# Iridium_9603_Lite_USB.net
KiCad netlist of a schematic drawn in EAGLE
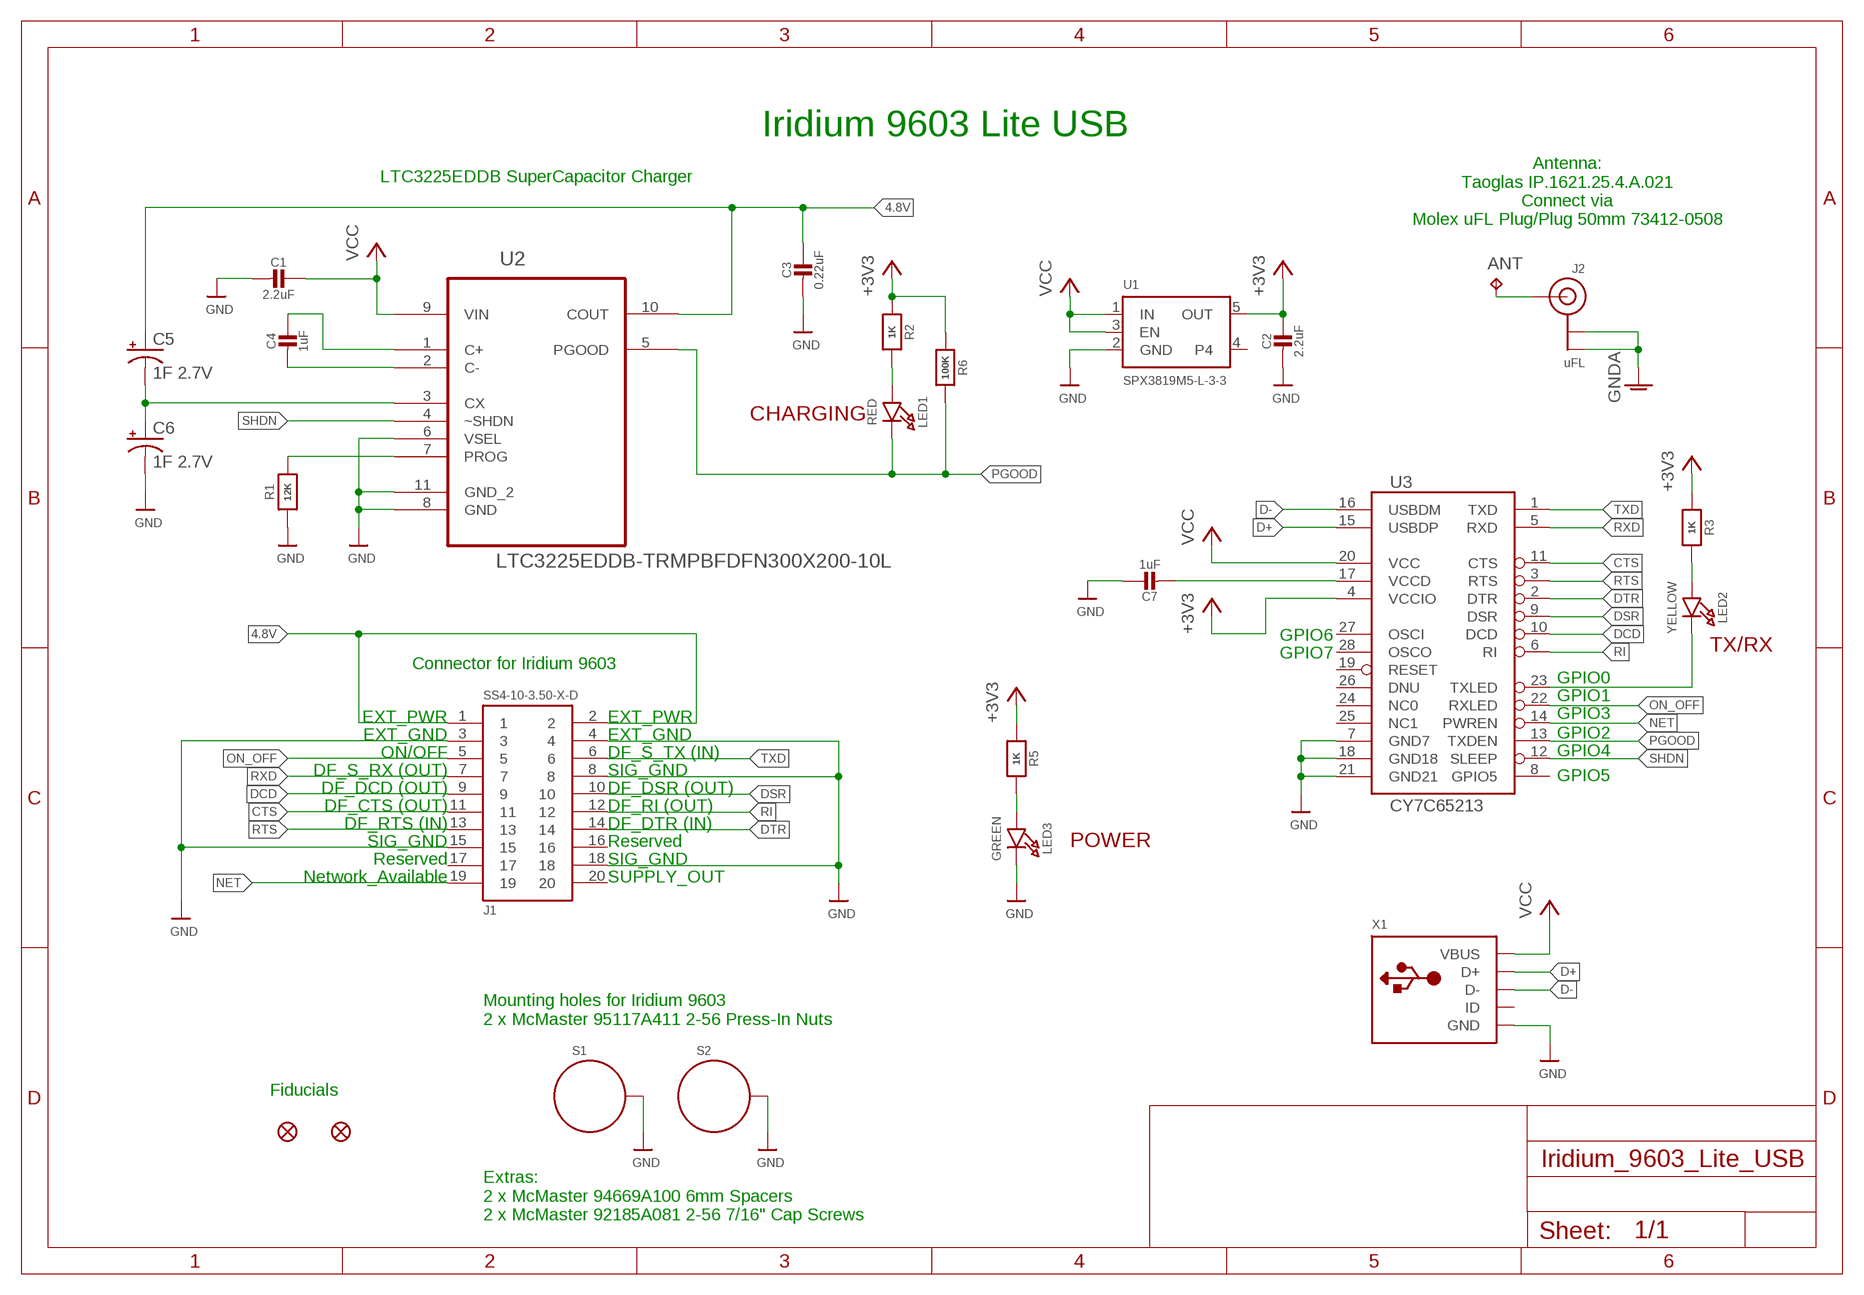
[diagram p0: schematic, sheet 1]

(export (version "E")
  (design (tool "Eeschema 10.0.6"))
  (components
    (comp (ref "ANT")
      (value "TPB2,54")
      (footprint "eagle-import:B2,54")
      (libsource (lib "eagle-import") (part "TPB2,54"))
    )
    (comp (ref "C1")
      (value "2.2uF")
      (footprint "eagle-import:0805-NO")
      (libsource (lib "eagle-import") (part "CAP_CERAMIC0805-NOOUTLINE"))
    )
    (comp (ref "C2")
      (value "2.2uF")
      (footprint "eagle-import:0805-NO")
      (libsource (lib "eagle-import") (part "CAP_CERAMIC0805-NOOUTLINE"))
    )
    (comp (ref "C3")
      (value "0.22uF")
      (footprint "eagle-import:0603-NO")
      (libsource (lib "eagle-import") (part "CAP_CERAMIC0603_NO"))
    )
    (comp (ref "C4")
      (value "1uF")
      (footprint "eagle-import:0603-NO")
      (libsource (lib "eagle-import") (part "CAP_CERAMIC0603_NO"))
    )
    (comp (ref "C5")
      (value "1F 2.7V")
      (footprint "eagle-import:CPOL-RADIAL-1F-2.7V")
      (libsource (lib "eagle-import") (part "1F-2.7V(PTH)CPOL-RADIAL-1H-2.7V"))
    )
    (comp (ref "C6")
      (value "1F 2.7V")
      (footprint "eagle-import:CPOL-RADIAL-1F-2.7V")
      (libsource (lib "eagle-import") (part "1F-2.7V(PTH)CPOL-RADIAL-1H-2.7V"))
    )
    (comp (ref "C7")
      (value "1uF")
      (footprint "eagle-import:0603-NO")
      (libsource (lib "eagle-import") (part "CAP_CERAMIC0603_NO"))
    )
    (comp (ref "FD1")
      (value "FIDUCIAL1X2")
      (footprint "eagle-import:FIDUCIAL-1X2")
      (libsource (lib "eagle-import") (part "FIDUCIAL1X2"))
    )
    (comp (ref "FD2")
      (value "FIDUCIAL1X2")
      (footprint "eagle-import:FIDUCIAL-1X2")
      (libsource (lib "eagle-import") (part "FIDUCIAL1X2"))
    )
    (comp (ref "J1")
      (value "SS4-10-3.50-X-D")
      (footprint "eagle-import:SS4-10-3.50-X-D")
      (libsource (lib "eagle-import") (part "SS4-10-3.50-X-D"))
    )
    (comp (ref "J2")
      (value "uFL")
      (footprint "eagle-import:U.FL")
      (libsource (lib "eagle-import") (part "ANTENNA_U.FL"))
    )
    (comp (ref "LED1")
      (value "RED")
      (footprint "eagle-import:CHIPLED_0805_NOOUTLINE")
      (libsource (lib "eagle-import") (part "LED0805_NOOUTLINE"))
    )
    (comp (ref "LED2")
      (value "YELLOW")
      (footprint "eagle-import:CHIPLED_0805_NOOUTLINE")
      (libsource (lib "eagle-import") (part "LED0805_NOOUTLINE"))
    )
    (comp (ref "LED3")
      (value "GREEN")
      (footprint "eagle-import:CHIPLED_0805_NOOUTLINE")
      (libsource (lib "eagle-import") (part "LED0805_NOOUTLINE"))
    )
    (comp (ref "R1")
      (value "12K")
      (footprint "eagle-import:0805-NO")
      (libsource (lib "eagle-import") (part "RESISTOR0805_NOOUTLINE"))
    )
    (comp (ref "R2")
      (value "1K")
      (footprint "eagle-import:0603-NO")
      (libsource (lib "eagle-import") (part "RESISTOR_0603_NOOUT"))
    )
    (comp (ref "R3")
      (value "1K")
      (footprint "eagle-import:0603-NO")
      (libsource (lib "eagle-import") (part "RESISTOR_0603_NOOUT"))
    )
    (comp (ref "R5")
      (value "1K")
      (footprint "eagle-import:0603-NO")
      (libsource (lib "eagle-import") (part "RESISTOR_0603_NOOUT"))
    )
    (comp (ref "R6")
      (value "100K")
      (footprint "eagle-import:0603-NO")
      (libsource (lib "eagle-import") (part "RESISTOR_0603_NOOUT"))
    )
    (comp (ref "S1")
      (value "STANDOFF_ELECTRICALMCMASTER-95117A411")
      (footprint "eagle-import:STANDOFF-ELECTRICAL-MCMASTER-95117A411")
      (libsource (lib "eagle-import") (part "STANDOFF_ELECTRICALMCMASTER-95117A411"))
    )
    (comp (ref "S2")
      (value "STANDOFF_ELECTRICALMCMASTER-95117A411")
      (footprint "eagle-import:STANDOFF-ELECTRICAL-MCMASTER-95117A411")
      (libsource (lib "eagle-import") (part "STANDOFF_ELECTRICALMCMASTER-95117A411"))
    )
    (comp (ref "U1")
      (value "SPX3819M5-L-3-3")
      (footprint "eagle-import:SOT23-5")
      (libsource (lib "eagle-import") (part "VREG_SOT23-5"))
    )
    (comp (ref "U2")
      (value "LTC3225EDDB-TRMPBFDFN300X200-10L")
      (footprint "eagle-import:DFN300X200-10L")
      (libsource (lib "eagle-import") (part "LTC3225EDDB-TRMPBFDFN300X200-10L"))
    )
    (comp (ref "U3")
      (value "CY7C65213")
      (footprint "eagle-import:SSOP28DB")
      (libsource (lib "eagle-import") (part "CY7C65213"))
    )
    (comp (ref "X1")
      (value "USBFCI_10103594_MILL")
      (footprint "eagle-import:FCI_10103594_MILL")
      (libsource (lib "eagle-import") (part "USBFCI_10103594_MILL"))
    )
  )
  (nets
    (net (code "1") (name "+3V3") (class "Default")
      (node (ref "C2") (pin "1") (pinfunction "1_1") (pintype "passive"))
      (node (ref "R2") (pin "1") (pinfunction "1_1") (pintype "passive"))
      (node (ref "R3") (pin "1") (pinfunction "1_1") (pintype "passive"))
      (node (ref "R5") (pin "1") (pinfunction "1_1") (pintype "passive"))
      (node (ref "R6") (pin "1") (pinfunction "1_1") (pintype "passive"))
      (node (ref "U1") (pin "5") (pinfunction "OUT_5") (pintype "power_in"))
      (node (ref "U3") (pin "4") (pinfunction "VCCIO_4") (pintype "power_in"))
    )
    (net (code "2") (name "/NC1") (class "Default")
      (node (ref "U3") (pin "25") (pinfunction "NC1_25") (pintype "power_in"))
    )
    (net (code "3") (name "4.8V") (class "Default")
      (node (ref "C3") (pin "1") (pinfunction "1_1") (pintype "passive"))
      (node (ref "C5") (pin "+") (pinfunction "+_+") (pintype "passive"))
      (node (ref "J1") (pin "1") (pinfunction "1_1") (pintype "bidirectional"))
      (node (ref "J1") (pin "2") (pinfunction "2_2") (pintype "bidirectional"))
      (node (ref "U2") (pin "10") (pinfunction "COUT_10") (pintype "output"))
    )
    (net (code "4") (name "CTS") (class "Default")
      (node (ref "J1") (pin "11") (pinfunction "11_11") (pintype "bidirectional"))
      (node (ref "U3") (pin "11") (pinfunction "CTS_11") (pintype "input"))
    )
    (net (code "5") (name "D+") (class "Default")
      (node (ref "U3") (pin "15") (pinfunction "USBDP_15") (pintype "bidirectional"))
      (node (ref "X1") (pin "D+") (pinfunction "D+_D+") (pintype "bidirectional"))
    )
    (net (code "6") (name "D-") (class "Default")
      (node (ref "U3") (pin "16") (pinfunction "USBDM_16") (pintype "bidirectional"))
      (node (ref "X1") (pin "D-") (pinfunction "D-_D-") (pintype "bidirectional"))
    )
    (net (code "7") (name "DCD") (class "Default")
      (node (ref "J1") (pin "9") (pinfunction "9_9") (pintype "bidirectional"))
      (node (ref "U3") (pin "10") (pinfunction "DCD_10") (pintype "input"))
    )
    (net (code "8") (name "DSR") (class "Default")
      (node (ref "J1") (pin "10") (pinfunction "10_10") (pintype "bidirectional"))
      (node (ref "U3") (pin "9") (pinfunction "DSR_9") (pintype "input"))
    )
    (net (code "9") (name "DTR") (class "Default")
      (node (ref "J1") (pin "14") (pinfunction "14_14") (pintype "bidirectional"))
      (node (ref "U3") (pin "2") (pinfunction "DTR_2") (pintype "output"))
    )
    (net (code "10") (name "GND") (class "Default")
      (node (ref "C1") (pin "2") (pinfunction "2_2") (pintype "passive"))
      (node (ref "C2") (pin "2") (pinfunction "2_2") (pintype "passive"))
      (node (ref "C3") (pin "2") (pinfunction "2_2") (pintype "passive"))
      (node (ref "C6") (pin "-") (pinfunction "-_-") (pintype "passive"))
      (node (ref "C7") (pin "1") (pinfunction "1_1") (pintype "passive"))
      (node (ref "J1") (pin "15") (pinfunction "15_15") (pintype "bidirectional"))
      (node (ref "J1") (pin "18") (pinfunction "18_18") (pintype "bidirectional"))
      (node (ref "J1") (pin "3") (pinfunction "3_3") (pintype "bidirectional"))
      (node (ref "J1") (pin "4") (pinfunction "4_4") (pintype "bidirectional"))
      (node (ref "J1") (pin "8") (pinfunction "8_8") (pintype "bidirectional"))
      (node (ref "LED3") (pin "C") (pinfunction "C_C") (pintype "passive"))
      (node (ref "R1") (pin "1") (pinfunction "1_1") (pintype "passive"))
      (node (ref "S1") (pin "P1") (pinfunction "P$1_P1") (pintype "bidirectional"))
      (node (ref "S2") (pin "P1") (pinfunction "P$1_P1") (pintype "bidirectional"))
      (node (ref "U1") (pin "2") (pinfunction "GND_2") (pintype "power_in"))
      (node (ref "U2") (pin "11") (pinfunction "GND_2_11") (pintype "passive"))
      (node (ref "U2") (pin "6") (pinfunction "VSEL_6") (pintype "input"))
      (node (ref "U2") (pin "8") (pinfunction "GND_8") (pintype "passive"))
      (node (ref "U3") (pin "18") (pinfunction "GND18_18") (pintype "power_in"))
      (node (ref "U3") (pin "21") (pinfunction "GND21_21") (pintype "power_in"))
      (node (ref "U3") (pin "7") (pinfunction "GND7_7") (pintype "power_in"))
      (node (ref "X1") (pin "BASE@1") (pinfunction "GND_BASE@1") (pintype "power_in"))
      (node (ref "X1") (pin "BASE@2") (pinfunction "GND_BASE@2") (pintype "power_in"))
      (node (ref "X1") (pin "GND") (pinfunction "GND_GND") (pintype "power_in"))
      (node (ref "X1") (pin "SPRT@1") (pinfunction "GND_SPRT@1") (pintype "power_in"))
      (node (ref "X1") (pin "SPRT@2") (pinfunction "GND_SPRT@2") (pintype "power_in"))
      (node (ref "X1") (pin "SPRT@3") (pinfunction "GND_SPRT@3") (pintype "power_in"))
      (node (ref "X1") (pin "SPRT@4") (pinfunction "GND_SPRT@4") (pintype "power_in"))
    )
    (net (code "11") (name "GNDA") (class "Default")
      (node (ref "J2") (pin "1") (pinfunction "GND_1") (pintype "passive"))
      (node (ref "J2") (pin "2") (pinfunction "GND_2") (pintype "passive"))
    )
    (net (code "12") (name "NET") (class "Default")
      (node (ref "J1") (pin "19") (pinfunction "19_19") (pintype "bidirectional"))
      (node (ref "U3") (pin "14") (pinfunction "PWREN_14") (pintype "input"))
    )
    (net (code "13") (name "Net-(J2-SIGNAL)") (class "Default")
      (node (ref "ANT") (pin "TP") (pinfunction "TP_TP") (pintype "input"))
      (node (ref "J2") (pin "3") (pinfunction "SIGNAL_3") (pintype "passive"))
    )
    (net (code "14") (name "Net-(LED1-PadA)") (class "Default")
      (node (ref "LED1") (pin "A") (pinfunction "A_A") (pintype "passive"))
      (node (ref "R2") (pin "2") (pinfunction "2_2") (pintype "passive"))
    )
    (net (code "15") (name "Net-(LED2-PadA)") (class "Default")
      (node (ref "LED2") (pin "A") (pinfunction "A_A") (pintype "passive"))
      (node (ref "R3") (pin "2") (pinfunction "2_2") (pintype "passive"))
    )
    (net (code "16") (name "Net-(LED3-PadA)") (class "Default")
      (node (ref "LED3") (pin "A") (pinfunction "A_A") (pintype "passive"))
      (node (ref "R5") (pin "2") (pinfunction "2_2") (pintype "passive"))
    )
    (net (code "17") (name "Net-(U2-C+)") (class "Default")
      (node (ref "C4") (pin "1") (pinfunction "1_1") (pintype "passive"))
      (node (ref "U2") (pin "1") (pinfunction "C+_1") (pintype "passive"))
    )
    (net (code "18") (name "Net-(U2-C-)") (class "Default")
      (node (ref "C4") (pin "2") (pinfunction "2_2") (pintype "passive"))
      (node (ref "U2") (pin "2") (pinfunction "C-_2") (pintype "passive"))
    )
    (net (code "19") (name "Net-(U2-CX)") (class "Default")
      (node (ref "C5") (pin "-") (pinfunction "-_-") (pintype "passive"))
      (node (ref "C6") (pin "+") (pinfunction "+_+") (pintype "passive"))
      (node (ref "U2") (pin "3") (pinfunction "CX_3") (pintype "passive"))
    )
    (net (code "20") (name "Net-(U2-PROG)") (class "Default")
      (node (ref "R1") (pin "2") (pinfunction "2_2") (pintype "passive"))
      (node (ref "U2") (pin "7") (pinfunction "PROG_7") (pintype "input"))
    )
    (net (code "21") (name "Net-(U3-TXLED)") (class "Default")
      (node (ref "LED2") (pin "C") (pinfunction "C_C") (pintype "passive"))
      (node (ref "U3") (pin "23") (pinfunction "TXLED_23") (pintype "input"))
    )
    (net (code "22") (name "Net-(U3-VCCD)") (class "Default")
      (node (ref "C7") (pin "2") (pinfunction "2_2") (pintype "passive"))
      (node (ref "U3") (pin "17") (pinfunction "VCCD_17") (pintype "output"))
    )
    (net (code "23") (name "ON_OFF") (class "Default")
      (node (ref "J1") (pin "5") (pinfunction "5_5") (pintype "bidirectional"))
      (node (ref "U3") (pin "22") (pinfunction "RXLED_22") (pintype "input"))
    )
    (net (code "24") (name "PGOOD") (class "Default")
      (node (ref "LED1") (pin "C") (pinfunction "C_C") (pintype "passive"))
      (node (ref "R6") (pin "2") (pinfunction "2_2") (pintype "passive"))
      (node (ref "U2") (pin "5") (pinfunction "PGOOD_5") (pintype "output"))
      (node (ref "U3") (pin "13") (pinfunction "TXDEN_13") (pintype "input"))
    )
    (net (code "25") (name "RI") (class "Default")
      (node (ref "J1") (pin "12") (pinfunction "12_12") (pintype "bidirectional"))
      (node (ref "U3") (pin "6") (pinfunction "RI_6") (pintype "input"))
    )
    (net (code "26") (name "RTS") (class "Default")
      (node (ref "J1") (pin "13") (pinfunction "13_13") (pintype "bidirectional"))
      (node (ref "U3") (pin "3") (pinfunction "RTS_3") (pintype "output"))
    )
    (net (code "27") (name "RXD") (class "Default")
      (node (ref "J1") (pin "7") (pinfunction "7_7") (pintype "bidirectional"))
      (node (ref "U3") (pin "5") (pinfunction "RXD_5") (pintype "input"))
    )
    (net (code "28") (name "SHDN") (class "Default")
      (node (ref "U2") (pin "4") (pinfunction "~{SHDN}_4") (pintype "input"))
      (node (ref "U3") (pin "12") (pinfunction "SLEEP_12") (pintype "input"))
    )
    (net (code "29") (name "TXD") (class "Default")
      (node (ref "J1") (pin "6") (pinfunction "6_6") (pintype "bidirectional"))
      (node (ref "U3") (pin "1") (pinfunction "TXD_1") (pintype "output"))
    )
    (net (code "30") (name "VCC") (class "Default")
      (node (ref "C1") (pin "1") (pinfunction "1_1") (pintype "passive"))
      (node (ref "U1") (pin "1") (pinfunction "IN_1") (pintype "power_in"))
      (node (ref "U1") (pin "3") (pinfunction "EN_3") (pintype "input"))
      (node (ref "U2") (pin "9") (pinfunction "VIN_9") (pintype "power_in"))
      (node (ref "U3") (pin "20") (pinfunction "VCC_20") (pintype "power_in"))
      (node (ref "X1") (pin "VBUS") (pinfunction "VBUS_VBUS") (pintype "power_in"))
    )
    (net (code "31") (name "unconnected-(J1-Pad16)") (class "Default")
      (node (ref "J1") (pin "16") (pinfunction "16_16") (pintype "bidirectional"))
    )
    (net (code "32") (name "unconnected-(J1-Pad17)") (class "Default")
      (node (ref "J1") (pin "17") (pinfunction "17_17") (pintype "bidirectional"))
    )
    (net (code "33") (name "unconnected-(J1-Pad20)") (class "Default")
      (node (ref "J1") (pin "20") (pinfunction "20_20") (pintype "bidirectional"))
    )
    (net (code "34") (name "unconnected-(U1-P4-Pad4)") (class "Default")
      (node (ref "U1") (pin "4") (pinfunction "P4_4") (pintype "bidirectional"))
    )
    (net (code "35") (name "unconnected-(U3-DNU-Pad26)") (class "Default")
      (node (ref "U3") (pin "26") (pinfunction "DNU_26") (pintype "input"))
    )
    (net (code "36") (name "unconnected-(U3-GPIO5-Pad8)") (class "Default")
      (node (ref "U3") (pin "8") (pinfunction "GPIO5_8") (pintype "input"))
    )
    (net (code "37") (name "unconnected-(U3-NC0-Pad24)") (class "Default")
      (node (ref "U3") (pin "24") (pinfunction "NC0_24") (pintype "input"))
    )
    (net (code "38") (name "unconnected-(U3-OSCI-Pad27)") (class "Default")
      (node (ref "U3") (pin "27") (pinfunction "OSCI_27") (pintype "input"))
    )
    (net (code "39") (name "unconnected-(U3-OSCO-Pad28)") (class "Default")
      (node (ref "U3") (pin "28") (pinfunction "OSCO_28") (pintype "output"))
    )
    (net (code "40") (name "unconnected-(U3-RESET-Pad19)") (class "Default")
      (node (ref "U3") (pin "19") (pinfunction "RESET_19") (pintype "input"))
    )
    (net (code "41") (name "unconnected-(X1-PadID)") (class "Default")
      (node (ref "X1") (pin "ID") (pinfunction "ID_ID") (pintype "bidirectional"))
    )
  )
)
